# Fleet-Monitor-Ethernet.net
KiCad netlist of a schematic drawn in Altium Designer
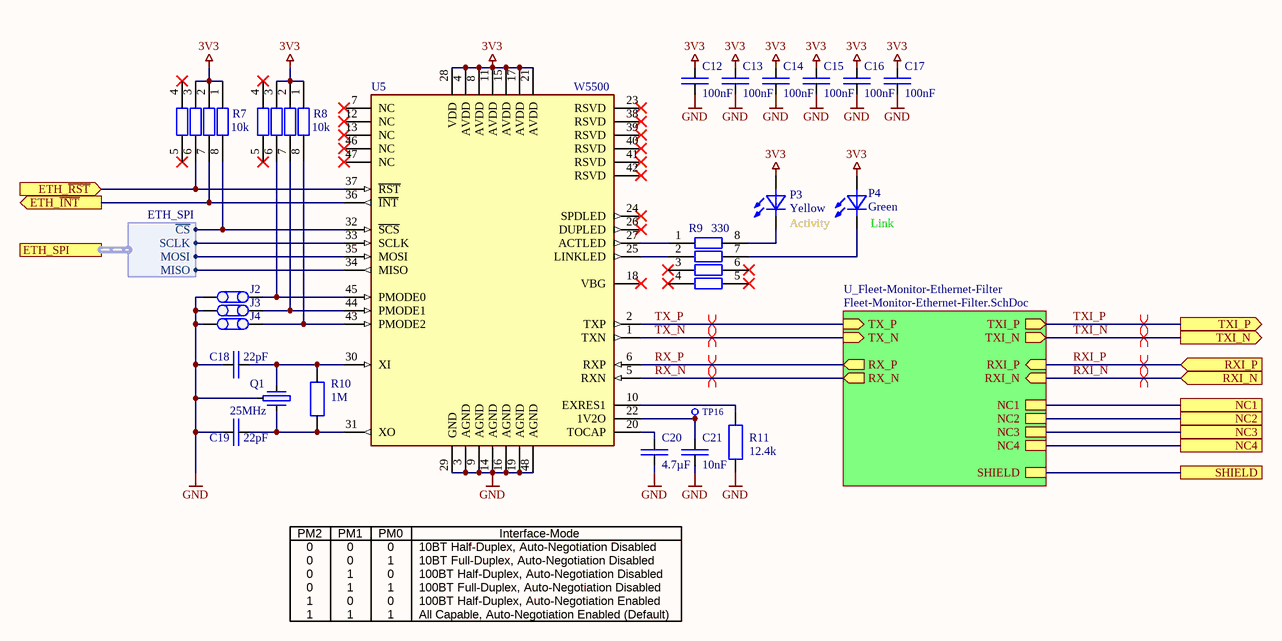
[diagram p0: Fleet-Monitor-Ethernet.SchDoc]

(export (version "E")
  (design (tool "Eeschema 10.0.6"))
  (components
    (comp (ref "C12")
      (value "100nF")
      (footprint "SMD Keramikkondensator 0603")
      (description "SMD Ceramic Capacitor E6")
      (libsource (lib "Ceramic Capacitors-E6") (part "E6 - 100nF"))
    )
    (comp (ref "C13")
      (value "100nF")
      (footprint "SMD Keramikkondensator 0603")
      (description "SMD Ceramic Capacitor E6")
      (libsource (lib "Ceramic Capacitors-E6") (part "E6 - 100nF"))
    )
    (comp (ref "C14")
      (value "100nF")
      (footprint "SMD Keramikkondensator 0603")
      (description "SMD Ceramic Capacitor E6")
      (libsource (lib "Ceramic Capacitors-E6") (part "E6 - 100nF"))
    )
    (comp (ref "C15")
      (value "100nF")
      (footprint "SMD Keramikkondensator 0603")
      (description "SMD Ceramic Capacitor E6")
      (libsource (lib "Ceramic Capacitors-E6") (part "E6 - 100nF"))
    )
    (comp (ref "C16")
      (value "100nF")
      (footprint "SMD Keramikkondensator 0603")
      (description "SMD Ceramic Capacitor E6")
      (libsource (lib "Ceramic Capacitors-E6") (part "E6 - 100nF"))
    )
    (comp (ref "C17")
      (value "100nF")
      (footprint "SMD Keramikkondensator 0603")
      (description "SMD Ceramic Capacitor E6")
      (libsource (lib "Ceramic Capacitors-E6") (part "E6 - 100nF"))
    )
    (comp (ref "C18")
      (value "22pF")
      (footprint "SMD Keramikkondensator 0603")
      (description "SMD Ceramic Capacitor E6")
      (libsource (lib "Ceramic Capacitors-E6") (part "E6 - 22pF"))
    )
    (comp (ref "C19")
      (value "22pF")
      (footprint "SMD Keramikkondensator 0603")
      (description "SMD Ceramic Capacitor E6")
      (libsource (lib "Ceramic Capacitors-E6") (part "E6 - 22pF"))
    )
    (comp (ref "C20")
      (value "4.7µF")
      (footprint "SMD Keramikkondensator 0603")
      (description "SMD Ceramic Capacitor E6")
      (libsource (lib "Ceramic Capacitors-E6") (part "E6 - 4.7uF"))
    )
    (comp (ref "C21")
      (value "10nF")
      (footprint "SMD Keramikkondensator 0603")
      (description "SMD Ceramic Capacitor E6")
      (libsource (lib "Ceramic Capacitors-E6") (part "E6 - 10nF"))
    )
    (comp (ref "J2")
      (value "X-Jumper (2 Fach)")
      (footprint "SMD Solder Jumper 1x2mm")
      (libsource (lib "FakeUSB_KellnCy") (part "X-Jumper (2 Fach)"))
    )
    (comp (ref "J3")
      (value "X-Jumper (2 Fach)")
      (footprint "SMD Solder Jumper 1x2mm")
      (libsource (lib "FakeUSB_KellnCy") (part "X-Jumper (2 Fach)"))
    )
    (comp (ref "J4")
      (value "X-Jumper (2 Fach)")
      (footprint "SMD Solder Jumper 1x2mm")
      (libsource (lib "FakeUSB_KellnCy") (part "X-Jumper (2 Fach)"))
    )
    (comp (ref "P3")
      (value "Yellow")
      (footprint "SMD LED 0603")
      (description "General Purpose LED")
      (libsource (lib "Fleet-Monitor") (part "LED Yellow 0603"))
    )
    (comp (ref "P4")
      (value "Green")
      (footprint "SMD LED 0603")
      (description "General Purpose LED")
      (libsource (lib "Fleet-Monitor") (part "LED Green 0603"))
    )
    (comp (ref "Q1")
      (value "25MHz")
      (footprint "SMD Crystal 2520")
      (description "SMD Crystal Resonators 25MHz 10ppm -40℃~85℃")
      (libsource (lib "Fleet-Monitor") (part "Crystal 25MHz 7E25000E20UCG"))
    )
    (comp (ref "R7")
      (value "10k")
      (footprint "SMD Widerstand Array 4-Fach 0603")
      (description "Isolated Resistor Array")
      (libsource (lib "Fleet-Monitor") (part "R-Array Single Quad E24 - 10k"))
    )
    (comp (ref "R8")
      (value "10k")
      (footprint "SMD Widerstand Array 4-Fach 0603")
      (description "Isolated Resistor Array")
      (libsource (lib "Fleet-Monitor") (part "R-Array Single Quad E24 - 10k"))
    )
    (comp (ref "R9")
      (value "330")
      (footprint "SMD Widerstand Array 4-Fach 0603")
      (description "Isolated Resistor Array")
      (libsource (lib "Fleet-Monitor") (part "R-Array Single Quad E24 - 330"))
    )
    (comp (ref "R10")
      (value "1M")
      (footprint "SMD Widerstand 0603")
      (description "SMD Chip Resistor E24")
      (libsource (lib "Fleet-Monitor") (part "E96 - 1M"))
    )
    (comp (ref "R11")
      (value "12.4k")
      (footprint "SMD Widerstand 0603")
      (description "SMD Chip Resistor E96")
      (libsource (lib "Resistors-E96") (part "E96 - 12.4k"))
    )
    (comp (ref "TP16")
      (value "X-TP")
      (footprint "SMD Testpunkt Ø1mm")
      (description "Testpunkt")
      (libsource (lib "VLD-Monitor_V1.0") (part "X-TP"))
    )
    (comp (ref "U5")
      (value "W5500")
      (footprint "SMD IC LQFP-48")
      (description "Ethernet Controller 10/100 Base-T/TX PHY SPI Interface 48-LQFP (7x7)")
      (libsource (lib "Fleet-Monitor") (part "W5500"))
    )
  )
  (nets
    (net (code "2") (name "/ETH_~{INT}") (class "Default")
      (node (ref "R7") (pin "7") (pinfunction "7_7") (pintype "passive"))
      (node (ref "U5") (pin "36") (pinfunction "~{INT}_36") (pintype "output"))
    )
    (net (code "3") (name "/ETH_~{RST}") (class "Default")
      (node (ref "R7") (pin "6") (pinfunction "6_6") (pintype "passive"))
      (node (ref "U5") (pin "37") (pinfunction "~{RST}_37") (pintype "input"))
    )
    (net (code "4") (name "/MISO") (class "Default")
      (node (ref "U5") (pin "34") (pinfunction "MISO_34") (pintype "output"))
    )
    (net (code "5") (name "/MOSI") (class "Default")
      (node (ref "U5") (pin "35") (pinfunction "MOSI_35") (pintype "input"))
    )
    (net (code "12") (name "/RX_N") (class "Default")
      (node (ref "U5") (pin "5") (pinfunction "RXN_5") (pintype "input"))
    )
    (net (code "13") (name "/RX_P") (class "Default")
      (node (ref "U5") (pin "6") (pinfunction "RXP_6") (pintype "input"))
    )
    (net (code "14") (name "/SCLK") (class "Default")
      (node (ref "U5") (pin "33") (pinfunction "SCLK_33") (pintype "input"))
    )
    (net (code "18") (name "/TX_N") (class "Default")
      (node (ref "U5") (pin "1") (pinfunction "TXN_1") (pintype "output"))
    )
    (net (code "19") (name "/TX_P") (class "Default")
      (node (ref "U5") (pin "2") (pinfunction "TXP_2") (pintype "output"))
    )
    (net (code "21") (name "/~{CS}") (class "Default")
      (node (ref "R7") (pin "8") (pinfunction "8_8") (pintype "passive"))
      (node (ref "U5") (pin "32") (pinfunction "~{SCS}_32") (pintype "input"))
    )
    (net (code "22") (name "3V3") (class "Default")
      (node (ref "C12") (pin "2") (pinfunction "2_2") (pintype "passive"))
      (node (ref "C13") (pin "2") (pinfunction "2_2") (pintype "passive"))
      (node (ref "C14") (pin "2") (pinfunction "2_2") (pintype "passive"))
      (node (ref "C15") (pin "2") (pinfunction "2_2") (pintype "passive"))
      (node (ref "C16") (pin "2") (pinfunction "2_2") (pintype "passive"))
      (node (ref "C17") (pin "2") (pinfunction "2_2") (pintype "passive"))
      (node (ref "P3") (pin "A") (pinfunction "A_A") (pintype "passive"))
      (node (ref "P4") (pin "A") (pinfunction "A_A") (pintype "passive"))
      (node (ref "R7") (pin "1") (pinfunction "1_1") (pintype "passive"))
      (node (ref "R7") (pin "2") (pinfunction "2_2") (pintype "passive"))
      (node (ref "R7") (pin "3") (pinfunction "3_3") (pintype "passive"))
      (node (ref "R8") (pin "1") (pinfunction "1_1") (pintype "passive"))
      (node (ref "R8") (pin "2") (pinfunction "2_2") (pintype "passive"))
      (node (ref "R8") (pin "3") (pinfunction "3_3") (pintype "passive"))
      (node (ref "U5") (pin "11") (pinfunction "AVDD_11") (pintype "power_in"))
      (node (ref "U5") (pin "15") (pinfunction "AVDD_15") (pintype "power_in"))
      (node (ref "U5") (pin "17") (pinfunction "AVDD_17") (pintype "power_in"))
      (node (ref "U5") (pin "21") (pinfunction "AVDD_21") (pintype "power_in"))
      (node (ref "U5") (pin "28") (pinfunction "VDD_28") (pintype "power_in"))
      (node (ref "U5") (pin "4") (pinfunction "AVDD_4") (pintype "power_in"))
      (node (ref "U5") (pin "8") (pinfunction "AVDD_8") (pintype "power_in"))
    )
    (net (code "23") (name "GND") (class "Default")
      (node (ref "C12") (pin "1") (pinfunction "1_1") (pintype "passive"))
      (node (ref "C13") (pin "1") (pinfunction "1_1") (pintype "passive"))
      (node (ref "C14") (pin "1") (pinfunction "1_1") (pintype "passive"))
      (node (ref "C15") (pin "1") (pinfunction "1_1") (pintype "passive"))
      (node (ref "C16") (pin "1") (pinfunction "1_1") (pintype "passive"))
      (node (ref "C17") (pin "1") (pinfunction "1_1") (pintype "passive"))
      (node (ref "C18") (pin "2") (pinfunction "2_2") (pintype "passive"))
      (node (ref "C19") (pin "2") (pinfunction "2_2") (pintype "passive"))
      (node (ref "C20") (pin "1") (pinfunction "1_1") (pintype "passive"))
      (node (ref "C21") (pin "1") (pinfunction "1_1") (pintype "passive"))
      (node (ref "J2") (pin "1") (pinfunction "1_1") (pintype "passive"))
      (node (ref "J3") (pin "1") (pinfunction "1_1") (pintype "passive"))
      (node (ref "J4") (pin "1") (pinfunction "1_1") (pintype "passive"))
      (node (ref "Q1") (pin "3") (pinfunction "3_3") (pintype "power_in"))
      (node (ref "R11") (pin "1") (pinfunction "1_1") (pintype "passive"))
      (node (ref "U5") (pin "14") (pinfunction "AGND_14") (pintype "power_in"))
      (node (ref "U5") (pin "16") (pinfunction "AGND_16") (pintype "power_in"))
      (node (ref "U5") (pin "19") (pinfunction "AGND_19") (pintype "power_in"))
      (node (ref "U5") (pin "29") (pinfunction "GND_29") (pintype "power_in"))
      (node (ref "U5") (pin "3") (pinfunction "AGND_3") (pintype "power_in"))
      (node (ref "U5") (pin "48") (pinfunction "AGND_48") (pintype "power_in"))
      (node (ref "U5") (pin "9") (pinfunction "AGND_9") (pintype "power_in"))
    )
    (net (code "24") (name "Net-(P3-PadK)") (class "Default")
      (node (ref "P3") (pin "K") (pinfunction "K_K") (pintype "passive"))
      (node (ref "R9") (pin "8") (pinfunction "8_8") (pintype "passive"))
    )
    (net (code "25") (name "Net-(P4-PadK)") (class "Default")
      (node (ref "P4") (pin "K") (pinfunction "K_K") (pintype "passive"))
      (node (ref "R9") (pin "7") (pinfunction "7_7") (pintype "passive"))
    )
    (net (code "26") (name "Net-(U5-1V2O)") (class "Default")
      (node (ref "C21") (pin "2") (pinfunction "2_2") (pintype "passive"))
      (node (ref "TP16") (pin "1") (pinfunction "1_1") (pintype "passive"))
      (node (ref "U5") (pin "22") (pinfunction "1V2O_22") (pintype "power_in"))
    )
    (net (code "27") (name "Net-(U5-ACTLED)") (class "Default")
      (node (ref "R9") (pin "1") (pinfunction "1_1") (pintype "passive"))
      (node (ref "U5") (pin "27") (pinfunction "ACTLED_27") (pintype "output"))
    )
    (net (code "28") (name "Net-(U5-EXRES1)") (class "Default")
      (node (ref "R11") (pin "2") (pinfunction "2_2") (pintype "passive"))
      (node (ref "U5") (pin "10") (pinfunction "EXRES1_10") (pintype "passive"))
    )
    (net (code "29") (name "Net-(U5-LINKLED)") (class "Default")
      (node (ref "R9") (pin "2") (pinfunction "2_2") (pintype "passive"))
      (node (ref "U5") (pin "25") (pinfunction "LINKLED_25") (pintype "output"))
    )
    (net (code "30") (name "Net-(U5-PMODE0)") (class "Default")
      (node (ref "J2") (pin "2") (pinfunction "2_2") (pintype "passive"))
      (node (ref "R8") (pin "6") (pinfunction "6_6") (pintype "passive"))
      (node (ref "U5") (pin "45") (pinfunction "PMODE0_45") (pintype "input"))
    )
    (net (code "31") (name "Net-(U5-PMODE1)") (class "Default")
      (node (ref "J3") (pin "2") (pinfunction "2_2") (pintype "passive"))
      (node (ref "R8") (pin "7") (pinfunction "7_7") (pintype "passive"))
      (node (ref "U5") (pin "44") (pinfunction "PMODE1_44") (pintype "input"))
    )
    (net (code "32") (name "Net-(U5-PMODE2)") (class "Default")
      (node (ref "J4") (pin "2") (pinfunction "2_2") (pintype "passive"))
      (node (ref "R8") (pin "8") (pinfunction "8_8") (pintype "passive"))
      (node (ref "U5") (pin "43") (pinfunction "PMODE2_43") (pintype "input"))
    )
    (net (code "33") (name "Net-(U5-TOCAP)") (class "Default")
      (node (ref "C20") (pin "2") (pinfunction "2_2") (pintype "passive"))
      (node (ref "U5") (pin "20") (pinfunction "TOCAP_20") (pintype "power_in"))
    )
    (net (code "34") (name "Net-(U5-XI)") (class "Default")
      (node (ref "C18") (pin "1") (pinfunction "1_1") (pintype "passive"))
      (node (ref "Q1") (pin "1") (pinfunction "1_1") (pintype "passive"))
      (node (ref "R10") (pin "1") (pinfunction "1_1") (pintype "passive"))
      (node (ref "U5") (pin "30") (pinfunction "XI_30") (pintype "input"))
    )
    (net (code "35") (name "Net-(U5-XO)") (class "Default")
      (node (ref "C19") (pin "1") (pinfunction "1_1") (pintype "passive"))
      (node (ref "Q1") (pin "2") (pinfunction "2_2") (pintype "passive"))
      (node (ref "R10") (pin "2") (pinfunction "2_2") (pintype "passive"))
      (node (ref "U5") (pin "31") (pinfunction "XO_31") (pintype "output"))
    )
    (net (code "36") (name "unconnected-(R7-Pad4)") (class "Default")
      (node (ref "R7") (pin "4") (pinfunction "4_4") (pintype "passive+no_connect"))
    )
    (net (code "37") (name "unconnected-(R7-Pad5)") (class "Default")
      (node (ref "R7") (pin "5") (pinfunction "5_5") (pintype "passive+no_connect"))
    )
    (net (code "38") (name "unconnected-(R8-Pad4)") (class "Default")
      (node (ref "R8") (pin "4") (pinfunction "4_4") (pintype "passive+no_connect"))
    )
    (net (code "39") (name "unconnected-(R8-Pad5)") (class "Default")
      (node (ref "R8") (pin "5") (pinfunction "5_5") (pintype "passive+no_connect"))
    )
    (net (code "40") (name "unconnected-(R9-Pad3)") (class "Default")
      (node (ref "R9") (pin "3") (pinfunction "3_3") (pintype "passive+no_connect"))
    )
    (net (code "41") (name "unconnected-(R9-Pad4)") (class "Default")
      (node (ref "R9") (pin "4") (pinfunction "4_4") (pintype "passive+no_connect"))
    )
    (net (code "42") (name "unconnected-(R9-Pad5)") (class "Default")
      (node (ref "R9") (pin "5") (pinfunction "5_5") (pintype "passive+no_connect"))
    )
    (net (code "43") (name "unconnected-(R9-Pad6)") (class "Default")
      (node (ref "R9") (pin "6") (pinfunction "6_6") (pintype "passive+no_connect"))
    )
    (net (code "44") (name "unconnected-(U5-DUPLED-Pad26)") (class "Default")
      (node (ref "U5") (pin "26") (pinfunction "DUPLED_26") (pintype "output+no_connect"))
    )
    (net (code "45") (name "unconnected-(U5-NC-Pad7)") (class "Default")
      (node (ref "U5") (pin "7") (pinfunction "NC_7") (pintype "passive+no_connect"))
    )
    (net (code "46") (name "unconnected-(U5-NC-Pad12)") (class "Default")
      (node (ref "U5") (pin "12") (pinfunction "NC_12") (pintype "passive+no_connect"))
    )
    (net (code "47") (name "unconnected-(U5-NC-Pad13)") (class "Default")
      (node (ref "U5") (pin "13") (pinfunction "NC_13") (pintype "passive+no_connect"))
    )
    (net (code "48") (name "unconnected-(U5-NC-Pad46)") (class "Default")
      (node (ref "U5") (pin "46") (pinfunction "NC_46") (pintype "passive+no_connect"))
    )
    (net (code "49") (name "unconnected-(U5-NC-Pad47)") (class "Default")
      (node (ref "U5") (pin "47") (pinfunction "NC_47") (pintype "passive+no_connect"))
    )
    (net (code "50") (name "unconnected-(U5-RSVD-Pad23)") (class "Default")
      (node (ref "U5") (pin "23") (pinfunction "RSVD_23") (pintype "passive+no_connect"))
    )
    (net (code "51") (name "unconnected-(U5-RSVD-Pad38)") (class "Default")
      (node (ref "U5") (pin "38") (pinfunction "RSVD_38") (pintype "passive+no_connect"))
    )
    (net (code "52") (name "unconnected-(U5-RSVD-Pad39)") (class "Default")
      (node (ref "U5") (pin "39") (pinfunction "RSVD_39") (pintype "passive+no_connect"))
    )
    (net (code "53") (name "unconnected-(U5-RSVD-Pad40)") (class "Default")
      (node (ref "U5") (pin "40") (pinfunction "RSVD_40") (pintype "passive+no_connect"))
    )
    (net (code "54") (name "unconnected-(U5-RSVD-Pad41)") (class "Default")
      (node (ref "U5") (pin "41") (pinfunction "RSVD_41") (pintype "passive+no_connect"))
    )
    (net (code "55") (name "unconnected-(U5-RSVD-Pad42)") (class "Default")
      (node (ref "U5") (pin "42") (pinfunction "RSVD_42") (pintype "passive+no_connect"))
    )
    (net (code "56") (name "unconnected-(U5-SPDLED-Pad24)") (class "Default")
      (node (ref "U5") (pin "24") (pinfunction "SPDLED_24") (pintype "output+no_connect"))
    )
    (net (code "57") (name "unconnected-(U5-VBG-Pad18)") (class "Default")
      (node (ref "U5") (pin "18") (pinfunction "VBG_18") (pintype "passive+no_connect"))
    )
  )
)
